# LED_Controller.net
KiCad netlist of a schematic drawn in Altium Designer
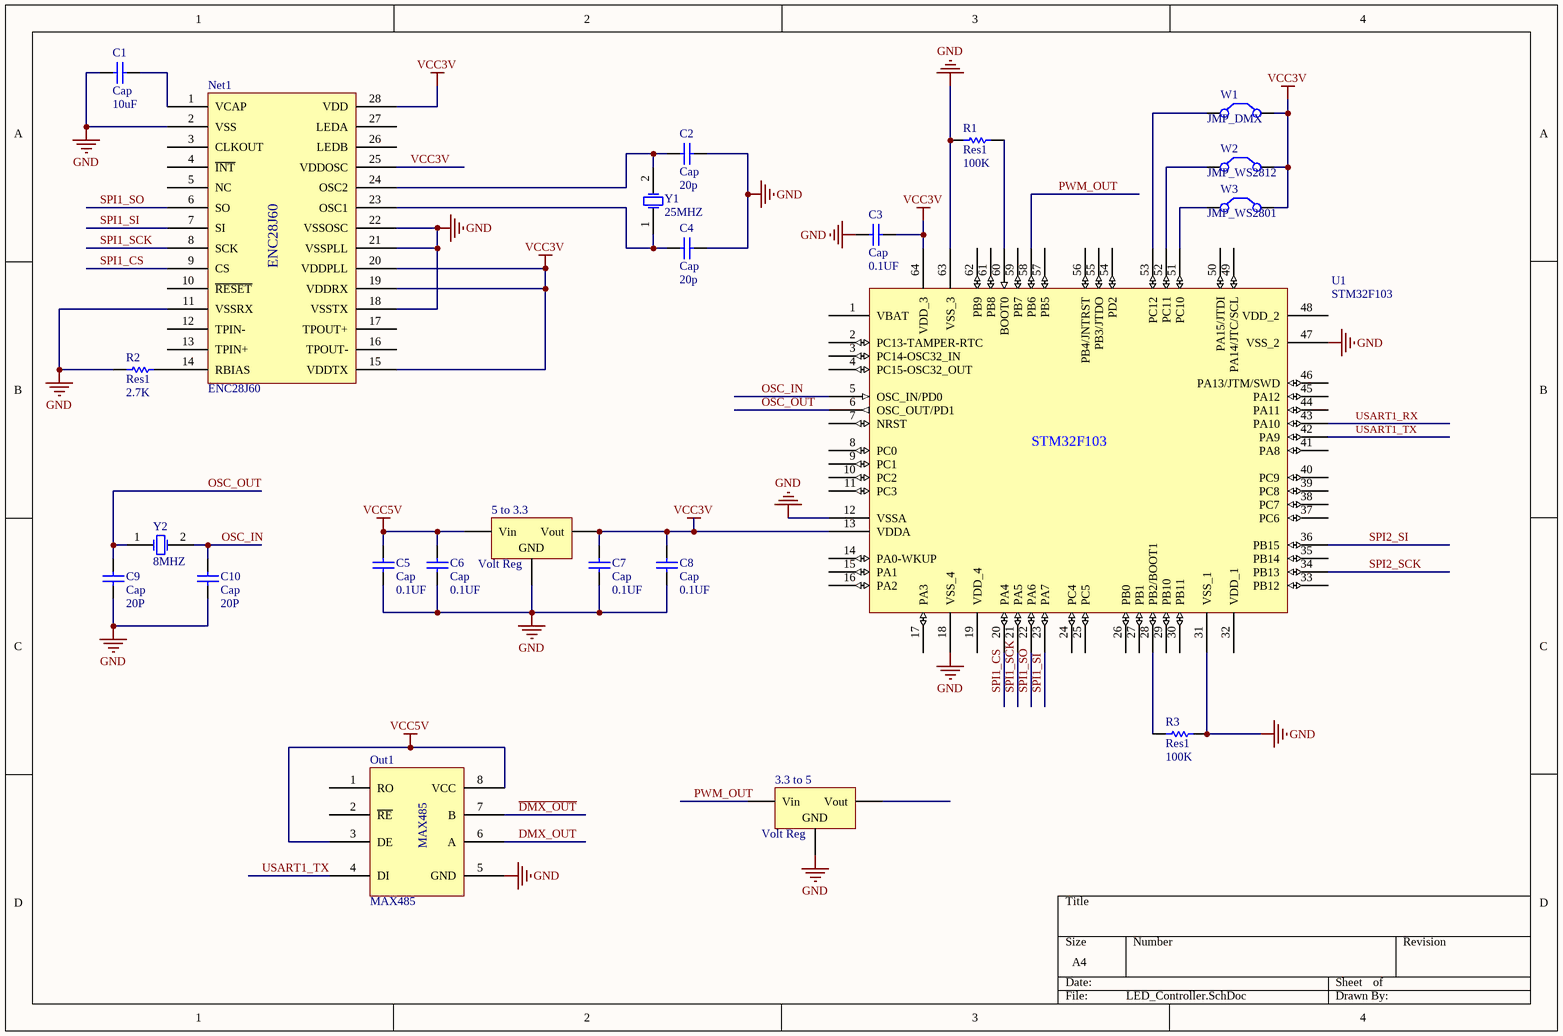
[diagram p0: LED_Controller.SchDoc]

(export (version "E")
  (design (tool "Eeschema 10.0.6"))
  (components
    (comp (ref "3.3 to 5")
      (value "Volt Reg")
      (footprint "D2PAK_N")
      (description "Voltage Regulator")
      (fields (field (name "PUBLISHER") "Altium Limited"))
      (libsource (lib "Miscellaneous Devices") (part "Volt Reg"))
    )
    (comp (ref "5 to 3.3")
      (value "Volt Reg")
      (footprint "D2PAK_N")
      (description "Voltage Regulator")
      (fields (field (name "PUBLISHER") "Altium Limited"))
      (libsource (lib "Miscellaneous Devices") (part "Volt Reg"))
    )
    (comp (ref "C1")
      (value "Cap")
      (footprint "RAD-0.3")
      (description "Capacitor")
      (fields (field (name "ALTIUM_VALUE") "10uF") (field (name "PUBLISHER") "Altium Limited"))
      (libsource (lib "Miscellaneous Devices") (part "Cap"))
    )
    (comp (ref "C2")
      (value "Cap")
      (footprint "RAD-0.3")
      (description "Capacitor")
      (fields (field (name "ALTIUM_VALUE") "20p") (field (name "PUBLISHER") "Altium Limited"))
      (libsource (lib "Miscellaneous Devices") (part "Cap"))
    )
    (comp (ref "C3")
      (value "Cap")
      (footprint "RAD-0.3")
      (description "Capacitor")
      (fields (field (name "ALTIUM_VALUE") "0.1UF") (field (name "PUBLISHER") "Altium Limited"))
      (libsource (lib "Miscellaneous Devices") (part "Cap"))
    )
    (comp (ref "C4")
      (value "Cap")
      (footprint "RAD-0.3")
      (description "Capacitor")
      (fields (field (name "ALTIUM_VALUE") "20p") (field (name "PUBLISHER") "Altium Limited"))
      (libsource (lib "Miscellaneous Devices") (part "Cap"))
    )
    (comp (ref "C5")
      (value "Cap")
      (footprint "RAD-0.3")
      (description "Capacitor")
      (fields (field (name "ALTIUM_VALUE") "0.1UF") (field (name "PUBLISHER") "Altium Limited"))
      (libsource (lib "Miscellaneous Devices") (part "Cap"))
    )
    (comp (ref "C6")
      (value "Cap")
      (footprint "RAD-0.3")
      (description "Capacitor")
      (fields (field (name "ALTIUM_VALUE") "0.1UF") (field (name "PUBLISHER") "Altium Limited"))
      (libsource (lib "Miscellaneous Devices") (part "Cap"))
    )
    (comp (ref "C7")
      (value "Cap")
      (footprint "RAD-0.3")
      (description "Capacitor")
      (fields (field (name "ALTIUM_VALUE") "0.1UF") (field (name "PUBLISHER") "Altium Limited"))
      (libsource (lib "Miscellaneous Devices") (part "Cap"))
    )
    (comp (ref "C8")
      (value "Cap")
      (footprint "RAD-0.3")
      (description "Capacitor")
      (fields (field (name "ALTIUM_VALUE") "0.1UF") (field (name "PUBLISHER") "Altium Limited"))
      (libsource (lib "Miscellaneous Devices") (part "Cap"))
    )
    (comp (ref "C9")
      (value "Cap")
      (footprint "RAD-0.3")
      (description "Capacitor")
      (fields (field (name "ALTIUM_VALUE") "20P") (field (name "PUBLISHER") "Altium Limited"))
      (libsource (lib "Miscellaneous Devices") (part "Cap"))
    )
    (comp (ref "C10")
      (value "Cap")
      (footprint "RAD-0.3")
      (description "Capacitor")
      (fields (field (name "ALTIUM_VALUE") "20P") (field (name "PUBLISHER") "Altium Limited"))
      (libsource (lib "Miscellaneous Devices") (part "Cap"))
    )
    (comp (ref "Net1") (value "ENC28J60") (footprint "ENC28J60") (libsource (lib "Blue") (part "ENC28J60")))
    (comp (ref "Out1") (value "MAX485") (libsource (lib "Blue") (part "MAX485")))
    (comp (ref "R1")
      (value "Res1")
      (footprint "AXIAL-0.3")
      (description "Resistor")
      (fields (field (name "ALTIUM_VALUE") "100K") (field (name "PUBLISHER") "Altium Limited"))
      (libsource (lib "Miscellaneous Devices") (part "Res1"))
    )
    (comp (ref "R2")
      (value "Res1")
      (footprint "AXIAL-0.3")
      (description "Resistor")
      (fields (field (name "ALTIUM_VALUE") "2.7K") (field (name "PUBLISHER") "Altium Limited"))
      (libsource (lib "Miscellaneous Devices") (part "Res1"))
    )
    (comp (ref "R3")
      (value "Res1")
      (footprint "AXIAL-0.3")
      (description "Resistor")
      (fields (field (name "ALTIUM_VALUE") "100K") (field (name "PUBLISHER") "Altium Limited"))
      (libsource (lib "Miscellaneous Devices") (part "Res1"))
    )
    (comp (ref "U1")
      (value "STM32F103")
      (footprint "LQFP64_L")
      (description "STM32 ARM-based 32-bit MCU with xxx Kbytes Flash, 64-pin LQFP, Industrial Temperature")
      (fields (field (name "PUBLISHER") "Altium Limited"))
      (libsource (lib "Blue") (part "STM32F103R"))
    )
    (comp (ref "W1")
      (value "JMP_DMX")
      (footprint "RAD-0.2")
      (description "Jumper Wire")
      (fields (field (name "PUBLISHER") "Altium Limited"))
      (libsource (lib "Miscellaneous Devices") (part "Jumper"))
    )
    (comp (ref "W2")
      (value "JMP_WS2812")
      (footprint "RAD-0.2")
      (description "Jumper Wire")
      (fields (field (name "PUBLISHER") "Altium Limited"))
      (libsource (lib "Miscellaneous Devices") (part "Jumper"))
    )
    (comp (ref "W3")
      (value "JMP_WS2801")
      (footprint "RAD-0.2")
      (description "Jumper Wire")
      (fields (field (name "PUBLISHER") "Altium Limited"))
      (libsource (lib "Miscellaneous Devices") (part "Jumper"))
    )
    (comp (ref "Y1")
      (value "25MHZ")
      (footprint "R38")
      (description "Crystal Oscillator")
      (fields (field (name "PUBLISHER") "Altium Limited"))
      (libsource (lib "Miscellaneous Devices") (part "XTAL"))
    )
    (comp (ref "Y2")
      (value "8MHZ")
      (footprint "R38")
      (description "Crystal Oscillator")
      (fields (field (name "PUBLISHER") "Altium Limited"))
      (libsource (lib "Miscellaneous Devices") (part "XTAL"))
    )
  )
  (nets
    (net (code "1") (name "/DMX_OUT") (class "Default")
      (node (ref "Out1") (pin "6") (pinfunction "A_6") (pintype "passive"))
    )
    (net (code "2") (name "/OSC_IN") (class "Default")
      (node (ref "C10") (pin "1") (pinfunction "1_1") (pintype "passive"))
      (node (ref "U1") (pin "5") (pinfunction "OSC_IN/PD0_5") (pintype "input"))
      (node (ref "Y2") (pin "2") (pinfunction "OSC2_2") (pintype "passive"))
    )
    (net (code "3") (name "/OSC_OUT") (class "Default")
      (node (ref "C9") (pin "1") (pinfunction "1_1") (pintype "passive"))
      (node (ref "U1") (pin "6") (pinfunction "OSC_OUT/PD1_6") (pintype "output"))
      (node (ref "Y2") (pin "1") (pinfunction "OSC1_1") (pintype "passive"))
    )
    (net (code "4") (name "/PWM_OUT") (class "Default")
      (node (ref "3.3 to 5") (pin "1") (pinfunction "Vin_1") (pintype "passive"))
      (node (ref "U1") (pin "58") (pinfunction "PB6_58") (pintype "bidirectional"))
    )
    (net (code "5") (name "/SPI1_CS") (class "Default")
      (node (ref "Net1") (pin "9") (pinfunction "CS_9") (pintype "passive"))
      (node (ref "U1") (pin "20") (pinfunction "PA4_20") (pintype "bidirectional"))
    )
    (net (code "6") (name "/SPI1_SCK") (class "Default")
      (node (ref "Net1") (pin "8") (pinfunction "SCK_8") (pintype "passive"))
      (node (ref "U1") (pin "21") (pinfunction "PA5_21") (pintype "bidirectional"))
    )
    (net (code "7") (name "/SPI1_SI") (class "Default")
      (node (ref "Net1") (pin "7") (pinfunction "SI_7") (pintype "passive"))
      (node (ref "U1") (pin "23") (pinfunction "PA7_23") (pintype "bidirectional"))
    )
    (net (code "8") (name "/SPI1_SO") (class "Default")
      (node (ref "Net1") (pin "6") (pinfunction "SO_6") (pintype "passive"))
      (node (ref "U1") (pin "22") (pinfunction "PA6_22") (pintype "bidirectional"))
    )
    (net (code "9") (name "/SPI2_SCK") (class "Default")
      (node (ref "U1") (pin "34") (pinfunction "PB13_34") (pintype "bidirectional"))
    )
    (net (code "10") (name "/SPI2_SI") (class "Default")
      (node (ref "U1") (pin "36") (pinfunction "PB15_36") (pintype "bidirectional"))
    )
    (net (code "11") (name "/USART1_RX") (class "Default")
      (node (ref "U1") (pin "43") (pinfunction "PA10_43") (pintype "bidirectional"))
    )
    (net (code "12") (name "/USART1_TX") (class "Default")
      (node (ref "Out1") (pin "4") (pinfunction "DI_4") (pintype "passive"))
      (node (ref "U1") (pin "42") (pinfunction "PA9_42") (pintype "bidirectional"))
    )
    (net (code "13") (name "/~{DMX_OUT}") (class "Default")
      (node (ref "Out1") (pin "7") (pinfunction "B_7") (pintype "passive"))
    )
    (net (code "14") (name "GND") (class "Default")
      (node (ref "3.3 to 5") (pin "2") (pinfunction "GND_2") (pintype "passive"))
      (node (ref "5 to 3.3") (pin "2") (pinfunction "GND_2") (pintype "passive"))
      (node (ref "C1") (pin "1") (pinfunction "1_1") (pintype "passive"))
      (node (ref "C10") (pin "2") (pinfunction "2_2") (pintype "passive"))
      (node (ref "C2") (pin "2") (pinfunction "2_2") (pintype "passive"))
      (node (ref "C3") (pin "1") (pinfunction "1_1") (pintype "passive"))
      (node (ref "C4") (pin "2") (pinfunction "2_2") (pintype "passive"))
      (node (ref "C5") (pin "1") (pinfunction "1_1") (pintype "passive"))
      (node (ref "C6") (pin "1") (pinfunction "1_1") (pintype "passive"))
      (node (ref "C7") (pin "1") (pinfunction "1_1") (pintype "passive"))
      (node (ref "C8") (pin "1") (pinfunction "1_1") (pintype "passive"))
      (node (ref "C9") (pin "2") (pinfunction "2_2") (pintype "passive"))
      (node (ref "Net1") (pin "11") (pinfunction "VSSRX_11") (pintype "passive"))
      (node (ref "Net1") (pin "18") (pinfunction "VSSTX_18") (pintype "passive"))
      (node (ref "Net1") (pin "2") (pinfunction "VSS_2") (pintype "passive"))
      (node (ref "Net1") (pin "21") (pinfunction "VSSPLL_21") (pintype "passive"))
      (node (ref "Net1") (pin "22") (pinfunction "VSSOSC_22") (pintype "passive"))
      (node (ref "Out1") (pin "5") (pinfunction "GND_5") (pintype "passive"))
      (node (ref "R1") (pin "1") (pinfunction "1_1") (pintype "passive"))
      (node (ref "R2") (pin "1") (pinfunction "1_1") (pintype "passive"))
      (node (ref "R3") (pin "2") (pinfunction "2_2") (pintype "passive"))
      (node (ref "U1") (pin "12") (pinfunction "VSSA_12") (pintype "power_in"))
      (node (ref "U1") (pin "18") (pinfunction "VSS_4_18") (pintype "power_in"))
      (node (ref "U1") (pin "31") (pinfunction "VSS_1_31") (pintype "power_in"))
      (node (ref "U1") (pin "47") (pinfunction "VSS_2_47") (pintype "power_in"))
      (node (ref "U1") (pin "63") (pinfunction "VSS_3_63") (pintype "power_in"))
    )
    (net (code "15") (name "Net-(Net1-OSC1)") (class "Default")
      (node (ref "C4") (pin "1") (pinfunction "1_1") (pintype "passive"))
      (node (ref "Net1") (pin "23") (pinfunction "OSC1_23") (pintype "passive"))
      (node (ref "Y1") (pin "1") (pinfunction "OSC1_1") (pintype "passive"))
    )
    (net (code "16") (name "Net-(Net1-OSC2)") (class "Default")
      (node (ref "C2") (pin "1") (pinfunction "1_1") (pintype "passive"))
      (node (ref "Net1") (pin "24") (pinfunction "OSC2_24") (pintype "passive"))
      (node (ref "Y1") (pin "2") (pinfunction "OSC2_2") (pintype "passive"))
    )
    (net (code "17") (name "Net-(Net1-RBIAS)") (class "Default")
      (node (ref "Net1") (pin "14") (pinfunction "RBIAS_14") (pintype "passive"))
      (node (ref "R2") (pin "2") (pinfunction "2_2") (pintype "passive"))
    )
    (net (code "18") (name "Net-(Net1-VCAP)") (class "Default")
      (node (ref "C1") (pin "2") (pinfunction "2_2") (pintype "passive"))
      (node (ref "Net1") (pin "1") (pinfunction "VCAP_1") (pintype "passive"))
    )
    (net (code "19") (name "Net-(U1-BOOT0)") (class "Default")
      (node (ref "R1") (pin "2") (pinfunction "2_2") (pintype "passive"))
      (node (ref "U1") (pin "60") (pinfunction "BOOT0_60") (pintype "input"))
    )
    (net (code "20") (name "Net-(U1-PB2{slash}BOOT1)") (class "Default")
      (node (ref "R3") (pin "1") (pinfunction "1_1") (pintype "passive"))
      (node (ref "U1") (pin "28") (pinfunction "PB2/BOOT1_28") (pintype "bidirectional"))
    )
    (net (code "21") (name "Net-(U1-PC10)") (class "Default")
      (node (ref "U1") (pin "51") (pinfunction "PC10_51") (pintype "bidirectional"))
      (node (ref "W3") (pin "1") (pinfunction "C1_1") (pintype "passive"))
    )
    (net (code "22") (name "Net-(U1-PC11)") (class "Default")
      (node (ref "U1") (pin "52") (pinfunction "PC11_52") (pintype "bidirectional"))
      (node (ref "W2") (pin "1") (pinfunction "C1_1") (pintype "passive"))
    )
    (net (code "23") (name "Net-(U1-PC12)") (class "Default")
      (node (ref "U1") (pin "53") (pinfunction "PC12_53") (pintype "bidirectional"))
      (node (ref "W1") (pin "1") (pinfunction "C1_1") (pintype "passive"))
    )
    (net (code "24") (name "VCC3V") (class "Default")
      (node (ref "5 to 3.3") (pin "3") (pinfunction "Vout_3") (pintype "passive"))
      (node (ref "C3") (pin "2") (pinfunction "2_2") (pintype "passive"))
      (node (ref "C7") (pin "2") (pinfunction "2_2") (pintype "passive"))
      (node (ref "C8") (pin "2") (pinfunction "2_2") (pintype "passive"))
      (node (ref "Net1") (pin "15") (pinfunction "VDDTX_15") (pintype "passive"))
      (node (ref "Net1") (pin "19") (pinfunction "VDDRX_19") (pintype "passive"))
      (node (ref "Net1") (pin "20") (pinfunction "VDDPLL_20") (pintype "passive"))
      (node (ref "Net1") (pin "25") (pinfunction "VDDOSC_25") (pintype "passive"))
      (node (ref "Net1") (pin "28") (pinfunction "VDD_28") (pintype "passive"))
      (node (ref "U1") (pin "13") (pinfunction "VDDA_13") (pintype "power_in"))
      (node (ref "U1") (pin "64") (pinfunction "VDD_3_64") (pintype "power_in"))
      (node (ref "W1") (pin "2") (pinfunction "C2_2") (pintype "passive"))
      (node (ref "W2") (pin "2") (pinfunction "C2_2") (pintype "passive"))
      (node (ref "W3") (pin "2") (pinfunction "C2_2") (pintype "passive"))
    )
    (net (code "25") (name "VCC5V") (class "Default")
      (node (ref "5 to 3.3") (pin "1") (pinfunction "Vin_1") (pintype "passive"))
      (node (ref "C5") (pin "2") (pinfunction "2_2") (pintype "passive"))
      (node (ref "C6") (pin "2") (pinfunction "2_2") (pintype "passive"))
      (node (ref "Out1") (pin "3") (pinfunction "DE_3") (pintype "passive"))
      (node (ref "Out1") (pin "8") (pinfunction "VCC_8") (pintype "passive"))
    )
    (net (code "26") (name "unconnected-(3.3 to 5-Vout-Pad3)") (class "Default")
      (node (ref "3.3 to 5") (pin "3") (pinfunction "Vout_3") (pintype "passive"))
    )
    (net (code "27") (name "unconnected-(Net1-CLKOUT-Pad3)") (class "Default")
      (node (ref "Net1") (pin "3") (pinfunction "CLKOUT_3") (pintype "passive"))
    )
    (net (code "28") (name "unconnected-(Net1-LEDA-Pad27)") (class "Default")
      (node (ref "Net1") (pin "27") (pinfunction "LEDA_27") (pintype "passive"))
    )
    (net (code "29") (name "unconnected-(Net1-LEDB-Pad26)") (class "Default")
      (node (ref "Net1") (pin "26") (pinfunction "LEDB_26") (pintype "passive"))
    )
    (net (code "30") (name "unconnected-(Net1-NC-Pad5)") (class "Default")
      (node (ref "Net1") (pin "5") (pinfunction "NC_5") (pintype "passive"))
    )
    (net (code "31") (name "unconnected-(Net1-TPIN+-Pad13)") (class "Default")
      (node (ref "Net1") (pin "13") (pinfunction "TPIN+_13") (pintype "passive"))
    )
    (net (code "32") (name "unconnected-(Net1-TPIN--Pad12)") (class "Default")
      (node (ref "Net1") (pin "12") (pinfunction "TPIN-_12") (pintype "passive"))
    )
    (net (code "33") (name "unconnected-(Net1-TPOUT+-Pad17)") (class "Default")
      (node (ref "Net1") (pin "17") (pinfunction "TPOUT+_17") (pintype "passive"))
    )
    (net (code "34") (name "unconnected-(Net1-TPOUT--Pad16)") (class "Default")
      (node (ref "Net1") (pin "16") (pinfunction "TPOUT-_16") (pintype "passive"))
    )
    (net (code "35") (name "unconnected-(Net1-~{INT}-Pad4)") (class "Default")
      (node (ref "Net1") (pin "4") (pinfunction "~{INT}_4") (pintype "passive"))
    )
    (net (code "36") (name "unconnected-(Net1-~{RESET}-Pad10)") (class "Default")
      (node (ref "Net1") (pin "10") (pinfunction "~{RESET}_10") (pintype "passive"))
    )
    (net (code "37") (name "unconnected-(Out1-RO-Pad1)") (class "Default")
      (node (ref "Out1") (pin "1") (pinfunction "RO_1") (pintype "passive"))
    )
    (net (code "38") (name "unconnected-(Out1-~{RE}-Pad2)") (class "Default")
      (node (ref "Out1") (pin "2") (pinfunction "~{RE}_2") (pintype "passive"))
    )
    (net (code "39") (name "unconnected-(U1-NRST-Pad7)") (class "Default")
      (node (ref "U1") (pin "7") (pinfunction "NRST_7") (pintype "bidirectional"))
    )
    (net (code "40") (name "unconnected-(U1-PA0-WKUP-Pad14)") (class "Default")
      (node (ref "U1") (pin "14") (pinfunction "PA0-WKUP_14") (pintype "bidirectional"))
    )
    (net (code "41") (name "unconnected-(U1-PA1-Pad15)") (class "Default")
      (node (ref "U1") (pin "15") (pinfunction "PA1_15") (pintype "bidirectional"))
    )
    (net (code "42") (name "unconnected-(U1-PA2-Pad16)") (class "Default")
      (node (ref "U1") (pin "16") (pinfunction "PA2_16") (pintype "bidirectional"))
    )
    (net (code "43") (name "unconnected-(U1-PA3-Pad17)") (class "Default")
      (node (ref "U1") (pin "17") (pinfunction "PA3_17") (pintype "bidirectional"))
    )
    (net (code "44") (name "unconnected-(U1-PA8-Pad41)") (class "Default")
      (node (ref "U1") (pin "41") (pinfunction "PA8_41") (pintype "bidirectional"))
    )
    (net (code "45") (name "unconnected-(U1-PA11-Pad44)") (class "Default")
      (node (ref "U1") (pin "44") (pinfunction "PA11_44") (pintype "bidirectional"))
    )
    (net (code "46") (name "unconnected-(U1-PA12-Pad45)") (class "Default")
      (node (ref "U1") (pin "45") (pinfunction "PA12_45") (pintype "bidirectional"))
    )
    (net (code "47") (name "unconnected-(U1-PA13{slash}JTM{slash}SWD-Pad46)") (class "Default")
      (node (ref "U1") (pin "46") (pinfunction "PA13/JTM/SWD_46") (pintype "bidirectional"))
    )
    (net (code "48") (name "unconnected-(U1-PA14{slash}JTC{slash}SCL-Pad49)") (class "Default")
      (node (ref "U1") (pin "49") (pinfunction "PA14/JTC/SCL_49") (pintype "bidirectional"))
    )
    (net (code "49") (name "unconnected-(U1-PA15{slash}JTDI-Pad50)") (class "Default")
      (node (ref "U1") (pin "50") (pinfunction "PA15/JTDI_50") (pintype "bidirectional"))
    )
    (net (code "50") (name "unconnected-(U1-PB0-Pad26)") (class "Default")
      (node (ref "U1") (pin "26") (pinfunction "PB0_26") (pintype "bidirectional"))
    )
    (net (code "51") (name "unconnected-(U1-PB1-Pad27)") (class "Default")
      (node (ref "U1") (pin "27") (pinfunction "PB1_27") (pintype "bidirectional"))
    )
    (net (code "52") (name "unconnected-(U1-PB3{slash}JTDO-Pad55)") (class "Default")
      (node (ref "U1") (pin "55") (pinfunction "PB3/JTDO_55") (pintype "bidirectional"))
    )
    (net (code "53") (name "unconnected-(U1-PB4{slash}JNTRST-Pad56)") (class "Default")
      (node (ref "U1") (pin "56") (pinfunction "PB4/JNTRST_56") (pintype "bidirectional"))
    )
    (net (code "54") (name "unconnected-(U1-PB5-Pad57)") (class "Default")
      (node (ref "U1") (pin "57") (pinfunction "PB5_57") (pintype "bidirectional"))
    )
    (net (code "55") (name "unconnected-(U1-PB7-Pad59)") (class "Default")
      (node (ref "U1") (pin "59") (pinfunction "PB7_59") (pintype "bidirectional"))
    )
    (net (code "56") (name "unconnected-(U1-PB8-Pad61)") (class "Default")
      (node (ref "U1") (pin "61") (pinfunction "PB8_61") (pintype "bidirectional"))
    )
    (net (code "57") (name "unconnected-(U1-PB9-Pad62)") (class "Default")
      (node (ref "U1") (pin "62") (pinfunction "PB9_62") (pintype "bidirectional"))
    )
    (net (code "58") (name "unconnected-(U1-PB10-Pad29)") (class "Default")
      (node (ref "U1") (pin "29") (pinfunction "PB10_29") (pintype "bidirectional"))
    )
    (net (code "59") (name "unconnected-(U1-PB11-Pad30)") (class "Default")
      (node (ref "U1") (pin "30") (pinfunction "PB11_30") (pintype "bidirectional"))
    )
    (net (code "60") (name "unconnected-(U1-PB12-Pad33)") (class "Default")
      (node (ref "U1") (pin "33") (pinfunction "PB12_33") (pintype "bidirectional"))
    )
    (net (code "61") (name "unconnected-(U1-PB14-Pad35)") (class "Default")
      (node (ref "U1") (pin "35") (pinfunction "PB14_35") (pintype "bidirectional"))
    )
    (net (code "62") (name "unconnected-(U1-PC0-Pad8)") (class "Default")
      (node (ref "U1") (pin "8") (pinfunction "PC0_8") (pintype "bidirectional"))
    )
    (net (code "63") (name "unconnected-(U1-PC1-Pad9)") (class "Default")
      (node (ref "U1") (pin "9") (pinfunction "PC1_9") (pintype "bidirectional"))
    )
    (net (code "64") (name "unconnected-(U1-PC2-Pad10)") (class "Default")
      (node (ref "U1") (pin "10") (pinfunction "PC2_10") (pintype "bidirectional"))
    )
    (net (code "65") (name "unconnected-(U1-PC3-Pad11)") (class "Default")
      (node (ref "U1") (pin "11") (pinfunction "PC3_11") (pintype "bidirectional"))
    )
    (net (code "66") (name "unconnected-(U1-PC4-Pad24)") (class "Default")
      (node (ref "U1") (pin "24") (pinfunction "PC4_24") (pintype "bidirectional"))
    )
    (net (code "67") (name "unconnected-(U1-PC5-Pad25)") (class "Default")
      (node (ref "U1") (pin "25") (pinfunction "PC5_25") (pintype "bidirectional"))
    )
    (net (code "68") (name "unconnected-(U1-PC6-Pad37)") (class "Default")
      (node (ref "U1") (pin "37") (pinfunction "PC6_37") (pintype "bidirectional"))
    )
    (net (code "69") (name "unconnected-(U1-PC7-Pad38)") (class "Default")
      (node (ref "U1") (pin "38") (pinfunction "PC7_38") (pintype "bidirectional"))
    )
    (net (code "70") (name "unconnected-(U1-PC8-Pad39)") (class "Default")
      (node (ref "U1") (pin "39") (pinfunction "PC8_39") (pintype "bidirectional"))
    )
    (net (code "71") (name "unconnected-(U1-PC9-Pad40)") (class "Default")
      (node (ref "U1") (pin "40") (pinfunction "PC9_40") (pintype "bidirectional"))
    )
    (net (code "72") (name "unconnected-(U1-PC13-TAMPER-RTC-Pad2)") (class "Default")
      (node (ref "U1") (pin "2") (pinfunction "PC13-TAMPER-RTC_2") (pintype "bidirectional"))
    )
    (net (code "73") (name "unconnected-(U1-PC14-OSC32_IN-Pad3)") (class "Default")
      (node (ref "U1") (pin "3") (pinfunction "PC14-OSC32_IN_3") (pintype "bidirectional"))
    )
    (net (code "74") (name "unconnected-(U1-PC15-OSC32_OUT-Pad4)") (class "Default")
      (node (ref "U1") (pin "4") (pinfunction "PC15-OSC32_OUT_4") (pintype "bidirectional"))
    )
    (net (code "75") (name "unconnected-(U1-PD2-Pad54)") (class "Default")
      (node (ref "U1") (pin "54") (pinfunction "PD2_54") (pintype "bidirectional"))
    )
    (net (code "76") (name "unconnected-(U1-VBAT-Pad1)") (class "Default")
      (node (ref "U1") (pin "1") (pinfunction "VBAT_1") (pintype "power_in"))
    )
    (net (code "77") (name "unconnected-(U1-VDD_1-Pad32)") (class "Default")
      (node (ref "U1") (pin "32") (pinfunction "VDD_1_32") (pintype "power_in"))
    )
    (net (code "78") (name "unconnected-(U1-VDD_2-Pad48)") (class "Default")
      (node (ref "U1") (pin "48") (pinfunction "VDD_2_48") (pintype "power_in"))
    )
    (net (code "79") (name "unconnected-(U1-VDD_4-Pad19)") (class "Default")
      (node (ref "U1") (pin "19") (pinfunction "VDD_4_19") (pintype "power_in"))
    )
  )
)
